# MCU.net
KiCad netlist of a schematic drawn in Altium Designer
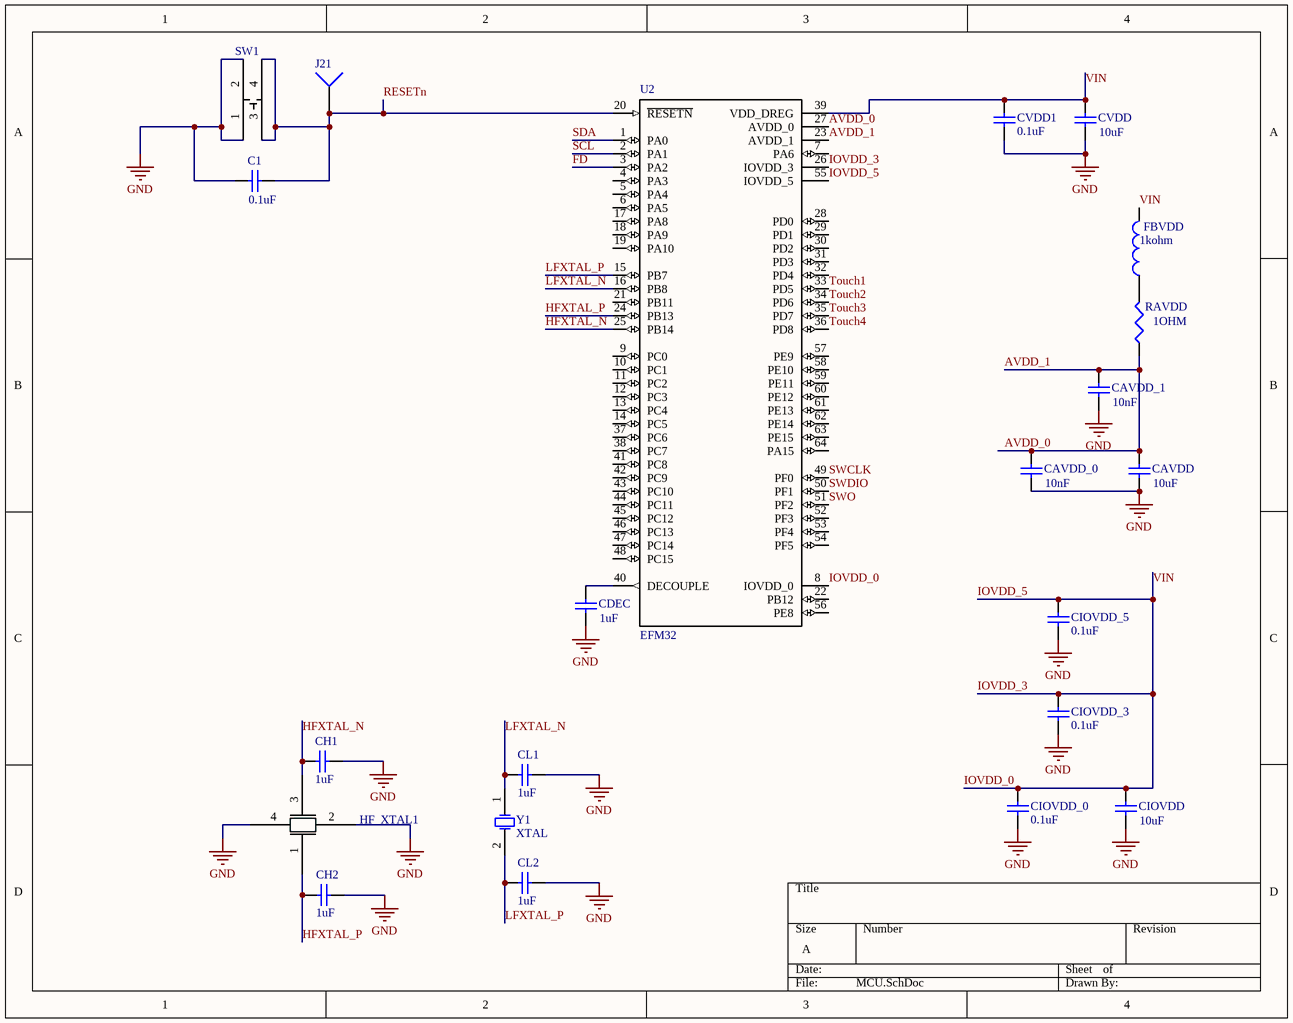
[diagram p0: MCU.SchDoc]

(export (version "E")
  (design (tool "Eeschema 10.0.6"))
  (components
    (comp (ref "C1")
      (value "0.1uF")
      (footprint "C1206")
      (description "CAP CER 0.1UF 16V Y5V 0603")
      (fields
        (field (name "DIGI-KEY PART NUMBER") "1276-1258-1-ND")
        (field (name "MANUFACTURER") "Samsung Electro-Mechanics")
      )
      (libsource (lib "Miscellaneous Devices") (part "Cap Semi"))
    )
    (comp (ref "CAVDD")
      (value "10uF")
      (footprint "C1206")
      (description "CL10A106MQ8NNNC")
      (fields
        (field (name "DIGI-KEY PART NUMBER") "1276-1119-1-ND")
        (field (name "MANUFACTURER") "Samsung Electro-Mechanics")
      )
      (libsource (lib "Miscellaneous Devices") (part "Cap Semi"))
    )
    (comp (ref "CAVDD_0")
      (value "10nF")
      (footprint "C1206")
      (description "CAP CER 10000PF 100V X7R 0603")
      (fields
        (field (name "DIGI-KEY PART NUMBER") "445-1305-1-ND")
        (field (name "MANUFACTURER") "TDK Corporation")
      )
      (libsource (lib "Miscellaneous Devices") (part "Cap Semi"))
    )
    (comp (ref "CAVDD_1")
      (value "10nF")
      (footprint "C1206")
      (description "CAP CER 10000PF 100V X7R 0603")
      (fields
        (field (name "DIGI-KEY PART NUMBER") "445-1305-1-ND")
        (field (name "MANUFACTURER") "TDK Corporation")
      )
      (libsource (lib "Miscellaneous Devices") (part "Cap Semi"))
    )
    (comp (ref "CDEC")
      (value "1uF")
      (footprint "C1206")
      (description "CAP CER 1UF 16V X7R 0603")
      (fields
        (field (name "DIGI-KEY PART NUMBER") "1276-6524-1-ND")
        (field (name "MANUFACTURER") "Samsung Electro-Mechanics")
      )
      (libsource (lib "Miscellaneous Devices") (part "Cap Semi"))
    )
    (comp (ref "CH1")
      (value "1uF")
      (footprint "C1206")
      (description "CAP CER 1UF 16V X7R 0603")
      (fields
        (field (name "DIGI-KEY PART NUMBER") "1276-6524-1-ND")
        (field (name "MANUFACTURER") "Samsung Electro-Mechanics")
      )
      (libsource (lib "Miscellaneous Devices") (part "Cap Semi"))
    )
    (comp (ref "CH2")
      (value "1uF")
      (footprint "C1206")
      (description "CAP CER 1UF 16V X7R 0603")
      (fields
        (field (name "DIGI-KEY PART NUMBER") "1276-6524-1-ND")
        (field (name "MANUFACTURER") "Samsung Electro-Mechanics")
      )
      (libsource (lib "Miscellaneous Devices") (part "Cap Semi"))
    )
    (comp (ref "CIOVDD")
      (value "10uF")
      (footprint "C1206")
      (description "CL10A106MQ8NNNC")
      (fields
        (field (name "DIGI-KEY PART NUMBER") "1276-1119-1-ND")
        (field (name "MANUFACTURER") "Samsung Electro-Mechanics")
      )
      (libsource (lib "Miscellaneous Devices") (part "Cap Semi"))
    )
    (comp (ref "CIOVDD_0")
      (value "0.1uF")
      (footprint "C1206")
      (description "CAP CER 0.1UF 16V Y5V 0603")
      (fields
        (field (name "DIGI-KEY PART NUMBER") "1276-1258-1-ND")
        (field (name "MANUFACTURER") "Samsung Electro-Mechanics")
      )
      (libsource (lib "Miscellaneous Devices") (part "Cap Semi"))
    )
    (comp (ref "CIOVDD_3")
      (value "0.1uF")
      (footprint "C1206")
      (description "CAP CER 0.1UF 16V Y5V 0603")
      (fields
        (field (name "DIGI-KEY PART NUMBER") "1276-1258-1-ND")
        (field (name "MANUFACTURER") "Samsung Electro-Mechanics")
      )
      (libsource (lib "Miscellaneous Devices") (part "Cap Semi"))
    )
    (comp (ref "CIOVDD_5")
      (value "0.1uF")
      (footprint "C1206")
      (description "CAP CER 0.1UF 16V Y5V 0603")
      (fields
        (field (name "DIGI-KEY PART NUMBER") "1276-1258-1-ND")
        (field (name "MANUFACTURER") "Samsung Electro-Mechanics")
      )
      (libsource (lib "Miscellaneous Devices") (part "Cap Semi"))
    )
    (comp (ref "CL1")
      (value "1uF")
      (footprint "C1206")
      (description "CAP CER 1UF 16V X7R 0603")
      (fields
        (field (name "DIGI-KEY PART NUMBER") "1276-6524-1-ND")
        (field (name "MANUFACTURER") "Samsung Electro-Mechanics")
      )
      (libsource (lib "Miscellaneous Devices") (part "Cap Semi"))
    )
    (comp (ref "CL2")
      (value "1uF")
      (footprint "C1206")
      (description "CAP CER 1UF 16V X7R 0603")
      (fields
        (field (name "DIGI-KEY PART NUMBER") "1276-6524-1-ND")
        (field (name "MANUFACTURER") "Samsung Electro-Mechanics")
      )
      (libsource (lib "Miscellaneous Devices") (part "Cap Semi"))
    )
    (comp (ref "CVDD")
      (value "10uF")
      (footprint "C1206")
      (description "CL10A106MQ8NNNC")
      (fields
        (field (name "DIGI-KEY PART NUMBER") "1276-1119-1-ND")
        (field (name "MANUFACTURER") "Samsung Electro-Mechanics")
      )
      (libsource (lib "Miscellaneous Devices") (part "Cap Semi"))
    )
    (comp (ref "CVDD1")
      (value "0.1uF")
      (footprint "C1206")
      (description "CAP CER 0.1UF 16V Y5V 0603")
      (fields
        (field (name "DIGI-KEY PART NUMBER") "1276-1258-1-ND")
        (field (name "MANUFACTURER") "Samsung Electro-Mechanics")
      )
      (libsource (lib "Miscellaneous Devices") (part "Cap Semi"))
    )
    (comp (ref "FBVDD")
      (value "1kohm")
      (footprint "0402-A")
      (description "FERRITE BEAD 1 KOHM 0603 1LN")
      (fields
        (field (name "DIGI-KEY PART NUMBER") "732-4484-1-ND")
        (field (name "MANUFACTURER") "Wurth Electronics Inc.")
      )
      (libsource (lib "Miscellaneous Devices") (part "Inductor"))
    )
    (comp (ref "HF_XTAL1")
      (value "Crystal_OSC")
      (footprint "HFXTAL")
      (fields
        (field (name "DIGI-KEY PART NUMBER") "1253-1120-1-ND")
        (field (name "MANUFACTURER") "Kyocera International Inc. Electronic Components")
        (field (name "MANUFACTURER PART NUMBER") "CX2016DB40000D0FLJCC")
      )
      (libsource (lib "EFM32PG12B500F1024GM48") (part "Crystal_OSC"))
    )
    (comp (ref "J21")
      (value "Socket")
      (footprint "PIN1")
      (fields (field (name "PUBLISHER") "Altium Limited"))
      (libsource (lib "Miscellaneous Connectors") (part "Socket"))
    )
    (comp (ref "RAVDD")
      (value "1OHM")
      (footprint "J1-0603")
      (description "RES SMD 1 OHM 1% 1/10W 0603")
      (fields (field (name "DIGI-KEY PART NUMBER") "311-1.00HRCT-ND") (field (name "MANUFACTURER") "Yageo"))
      (libsource (lib "Miscellaneous Devices") (part "Res3"))
    )
    (comp (ref "SW1")
      (value "Switch-PTS645")
      (footprint "Switch")
      (description "SWITCH TACTILE SPST-NO 0.05A 12V")
      (fields (field (name "DIGI-KEY PART NUMBER") "CKN9112CT-ND") (field (name "MANUFACTURER") "C&K"))
      (libsource (lib "EFM32PG12B500F1024GM48") (part "Switch-PTS645"))
    )
    (comp (ref "U2")
      (value "EFM32")
      (footprint "QFN-64")
      (description "IC MCU 32BIT 64KB FLASH 64QFN")
      (fields
        (field (name "DIGI-KEY PART NUMBER") "336-4841-1-ND")
        (field (name "MANUFACTURER") "Silicon Labs")
      )
      (libsource (lib "phone_cover_parts") (part "EFM32G232F128-QFP64"))
    )
    (comp (ref "Y1")
      (value "XTAL")
      (footprint "R38")
      (description "CRYSTAL 32.7680KHZ 7PF SMD")
      (fields
        (field (name "DIGI-KEY PART NUMBER") "535-9543-1-ND")
        (field (name "MANUFACTURER") "Abracon LLC")
      )
      (libsource (lib "Miscellaneous Devices") (part "XTAL"))
    )
  )
  (nets
    (net (code "1") (name "/AVDD_0") (class "Default")
      (node (ref "CAVDD") (pin "2") (pinfunction "2_2") (pintype "passive"))
      (node (ref "CAVDD_0") (pin "2") (pinfunction "2_2") (pintype "passive"))
      (node (ref "CAVDD_1") (pin "2") (pinfunction "2_2") (pintype "passive"))
      (node (ref "RAVDD") (pin "1") (pinfunction "1_1") (pintype "passive"))
      (node (ref "U2") (pin "23") (pinfunction "AVDD_1_23") (pintype "power_in"))
      (node (ref "U2") (pin "27") (pinfunction "AVDD_0_27") (pintype "power_in"))
    )
    (net (code "2") (name "/FD") (class "Default")
      (node (ref "U2") (pin "3") (pinfunction "PA2_3") (pintype "bidirectional"))
    )
    (net (code "3") (name "/HFXTAL_N") (class "Default")
      (node (ref "CH1") (pin "2") (pinfunction "2_2") (pintype "passive"))
      (node (ref "HF_XTAL1") (pin "3") (pinfunction "6_3") (pintype "passive"))
      (node (ref "U2") (pin "25") (pinfunction "PB14_25") (pintype "bidirectional"))
    )
    (net (code "4") (name "/HFXTAL_P") (class "Default")
      (node (ref "CH2") (pin "2") (pinfunction "2_2") (pintype "passive"))
      (node (ref "HF_XTAL1") (pin "1") (pinfunction "7_1") (pintype "passive"))
      (node (ref "U2") (pin "24") (pinfunction "PB13_24") (pintype "bidirectional"))
    )
    (net (code "5") (name "/IOVDD_0") (class "Default")
      (node (ref "CIOVDD") (pin "2") (pinfunction "2_2") (pintype "passive"))
      (node (ref "CIOVDD_0") (pin "2") (pinfunction "2_2") (pintype "passive"))
      (node (ref "CIOVDD_3") (pin "2") (pinfunction "2_2") (pintype "passive"))
      (node (ref "CIOVDD_5") (pin "2") (pinfunction "2_2") (pintype "passive"))
      (node (ref "CVDD") (pin "2") (pinfunction "2_2") (pintype "passive"))
      (node (ref "CVDD1") (pin "2") (pinfunction "2_2") (pintype "passive"))
      (node (ref "FBVDD") (pin "2") (pinfunction "2_2") (pintype "passive"))
      (node (ref "U2") (pin "26") (pinfunction "IOVDD_3_26") (pintype "power_in"))
      (node (ref "U2") (pin "39") (pinfunction "VDD_DREG_39") (pintype "power_in"))
      (node (ref "U2") (pin "55") (pinfunction "IOVDD_5_55") (pintype "power_in"))
      (node (ref "U2") (pin "8") (pinfunction "IOVDD_0_8") (pintype "power_in"))
    )
    (net (code "6") (name "/LFXTAL_N") (class "Default")
      (node (ref "CL1") (pin "2") (pinfunction "2_2") (pintype "passive"))
      (node (ref "U2") (pin "16") (pinfunction "PB8_16") (pintype "bidirectional"))
      (node (ref "Y1") (pin "1") (pinfunction "OSC1_1") (pintype "passive"))
    )
    (net (code "7") (name "/LFXTAL_P") (class "Default")
      (node (ref "CL2") (pin "1") (pinfunction "1_1") (pintype "passive"))
      (node (ref "U2") (pin "15") (pinfunction "PB7_15") (pintype "bidirectional"))
      (node (ref "Y1") (pin "2") (pinfunction "OSC2_2") (pintype "passive"))
    )
    (net (code "8") (name "/RESETn") (class "Default")
      (node (ref "C1") (pin "2") (pinfunction "2_2") (pintype "passive"))
      (node (ref "J21") (pin "1") (pinfunction "1_1") (pintype "passive"))
      (node (ref "SW1") (pin "3") (pinfunction "5_3") (pintype "passive"))
      (node (ref "SW1") (pin "4") (pinfunction "4_4") (pintype "passive"))
      (node (ref "U2") (pin "20") (pinfunction "~{RESETN}_20") (pintype "input"))
    )
    (net (code "9") (name "/SCL") (class "Default")
      (node (ref "U2") (pin "2") (pinfunction "PA1_2") (pintype "bidirectional"))
    )
    (net (code "10") (name "/SDA") (class "Default")
      (node (ref "U2") (pin "1") (pinfunction "PA0_1") (pintype "bidirectional"))
    )
    (net (code "11") (name "/SWCLK") (class "Default")
      (node (ref "U2") (pin "49") (pinfunction "PF0_49") (pintype "bidirectional"))
    )
    (net (code "12") (name "/SWDIO") (class "Default")
      (node (ref "U2") (pin "50") (pinfunction "PF1_50") (pintype "bidirectional"))
    )
    (net (code "13") (name "/SWO") (class "Default")
      (node (ref "U2") (pin "51") (pinfunction "PF2_51") (pintype "bidirectional"))
    )
    (net (code "14") (name "/Touch1") (class "Default")
      (node (ref "U2") (pin "33") (pinfunction "PD5_33") (pintype "bidirectional"))
    )
    (net (code "15") (name "/Touch2") (class "Default")
      (node (ref "U2") (pin "34") (pinfunction "PD6_34") (pintype "bidirectional"))
    )
    (net (code "16") (name "/Touch3") (class "Default")
      (node (ref "U2") (pin "35") (pinfunction "PD7_35") (pintype "bidirectional"))
    )
    (net (code "17") (name "/Touch4") (class "Default")
      (node (ref "U2") (pin "36") (pinfunction "PD8_36") (pintype "bidirectional"))
    )
    (net (code "18") (name "GND") (class "Default")
      (node (ref "C1") (pin "1") (pinfunction "1_1") (pintype "passive"))
      (node (ref "CAVDD") (pin "1") (pinfunction "1_1") (pintype "passive"))
      (node (ref "CAVDD_0") (pin "1") (pinfunction "1_1") (pintype "passive"))
      (node (ref "CAVDD_1") (pin "1") (pinfunction "1_1") (pintype "passive"))
      (node (ref "CDEC") (pin "1") (pinfunction "1_1") (pintype "passive"))
      (node (ref "CH1") (pin "1") (pinfunction "1_1") (pintype "passive"))
      (node (ref "CH2") (pin "1") (pinfunction "1_1") (pintype "passive"))
      (node (ref "CIOVDD") (pin "1") (pinfunction "1_1") (pintype "passive"))
      (node (ref "CIOVDD_0") (pin "1") (pinfunction "1_1") (pintype "passive"))
      (node (ref "CIOVDD_3") (pin "1") (pinfunction "1_1") (pintype "passive"))
      (node (ref "CIOVDD_5") (pin "1") (pinfunction "1_1") (pintype "passive"))
      (node (ref "CL1") (pin "1") (pinfunction "1_1") (pintype "passive"))
      (node (ref "CL2") (pin "2") (pinfunction "2_2") (pintype "passive"))
      (node (ref "CVDD") (pin "1") (pinfunction "1_1") (pintype "passive"))
      (node (ref "CVDD1") (pin "1") (pinfunction "1_1") (pintype "passive"))
      (node (ref "HF_XTAL1") (pin "2") (pinfunction "9_2") (pintype "passive"))
      (node (ref "HF_XTAL1") (pin "4") (pinfunction "8_4") (pintype "passive"))
      (node (ref "SW1") (pin "1") (pinfunction "5_1") (pintype "passive"))
      (node (ref "SW1") (pin "2") (pinfunction "6_2") (pintype "passive"))
    )
    (net (code "19") (name "Net-(FBVDD-Pad1)") (class "Default")
      (node (ref "FBVDD") (pin "1") (pinfunction "1_1") (pintype "passive"))
      (node (ref "RAVDD") (pin "2") (pinfunction "2_2") (pintype "passive"))
    )
    (net (code "20") (name "Net-(U2-DECOUPLE)") (class "Default")
      (node (ref "CDEC") (pin "2") (pinfunction "2_2") (pintype "passive"))
      (node (ref "U2") (pin "40") (pinfunction "DECOUPLE_40") (pintype "output"))
    )
    (net (code "21") (name "unconnected-(U2-PA3-Pad4)") (class "Default")
      (node (ref "U2") (pin "4") (pinfunction "PA3_4") (pintype "bidirectional"))
    )
    (net (code "22") (name "unconnected-(U2-PA4-Pad5)") (class "Default")
      (node (ref "U2") (pin "5") (pinfunction "PA4_5") (pintype "bidirectional"))
    )
    (net (code "23") (name "unconnected-(U2-PA5-Pad6)") (class "Default")
      (node (ref "U2") (pin "6") (pinfunction "PA5_6") (pintype "bidirectional"))
    )
    (net (code "24") (name "unconnected-(U2-PA6-Pad7)") (class "Default")
      (node (ref "U2") (pin "7") (pinfunction "PA6_7") (pintype "bidirectional"))
    )
    (net (code "25") (name "unconnected-(U2-PA8-Pad17)") (class "Default")
      (node (ref "U2") (pin "17") (pinfunction "PA8_17") (pintype "bidirectional"))
    )
    (net (code "26") (name "unconnected-(U2-PA9-Pad18)") (class "Default")
      (node (ref "U2") (pin "18") (pinfunction "PA9_18") (pintype "bidirectional"))
    )
    (net (code "27") (name "unconnected-(U2-PA10-Pad19)") (class "Default")
      (node (ref "U2") (pin "19") (pinfunction "PA10_19") (pintype "bidirectional"))
    )
    (net (code "28") (name "unconnected-(U2-PA15-Pad64)") (class "Default")
      (node (ref "U2") (pin "64") (pinfunction "PA15_64") (pintype "bidirectional"))
    )
    (net (code "29") (name "unconnected-(U2-PB11-Pad21)") (class "Default")
      (node (ref "U2") (pin "21") (pinfunction "PB11_21") (pintype "bidirectional"))
    )
    (net (code "30") (name "unconnected-(U2-PB12-Pad22)") (class "Default")
      (node (ref "U2") (pin "22") (pinfunction "PB12_22") (pintype "bidirectional"))
    )
    (net (code "31") (name "unconnected-(U2-PC0-Pad9)") (class "Default")
      (node (ref "U2") (pin "9") (pinfunction "PC0_9") (pintype "bidirectional"))
    )
    (net (code "32") (name "unconnected-(U2-PC1-Pad10)") (class "Default")
      (node (ref "U2") (pin "10") (pinfunction "PC1_10") (pintype "bidirectional"))
    )
    (net (code "33") (name "unconnected-(U2-PC2-Pad11)") (class "Default")
      (node (ref "U2") (pin "11") (pinfunction "PC2_11") (pintype "bidirectional"))
    )
    (net (code "34") (name "unconnected-(U2-PC3-Pad12)") (class "Default")
      (node (ref "U2") (pin "12") (pinfunction "PC3_12") (pintype "bidirectional"))
    )
    (net (code "35") (name "unconnected-(U2-PC4-Pad13)") (class "Default")
      (node (ref "U2") (pin "13") (pinfunction "PC4_13") (pintype "bidirectional"))
    )
    (net (code "36") (name "unconnected-(U2-PC5-Pad14)") (class "Default")
      (node (ref "U2") (pin "14") (pinfunction "PC5_14") (pintype "bidirectional"))
    )
    (net (code "37") (name "unconnected-(U2-PC6-Pad37)") (class "Default")
      (node (ref "U2") (pin "37") (pinfunction "PC6_37") (pintype "bidirectional"))
    )
    (net (code "38") (name "unconnected-(U2-PC7-Pad38)") (class "Default")
      (node (ref "U2") (pin "38") (pinfunction "PC7_38") (pintype "bidirectional"))
    )
    (net (code "39") (name "unconnected-(U2-PC8-Pad41)") (class "Default")
      (node (ref "U2") (pin "41") (pinfunction "PC8_41") (pintype "bidirectional"))
    )
    (net (code "40") (name "unconnected-(U2-PC9-Pad42)") (class "Default")
      (node (ref "U2") (pin "42") (pinfunction "PC9_42") (pintype "bidirectional"))
    )
    (net (code "41") (name "unconnected-(U2-PC10-Pad43)") (class "Default")
      (node (ref "U2") (pin "43") (pinfunction "PC10_43") (pintype "bidirectional"))
    )
    (net (code "42") (name "unconnected-(U2-PC11-Pad44)") (class "Default")
      (node (ref "U2") (pin "44") (pinfunction "PC11_44") (pintype "bidirectional"))
    )
    (net (code "43") (name "unconnected-(U2-PC12-Pad45)") (class "Default")
      (node (ref "U2") (pin "45") (pinfunction "PC12_45") (pintype "bidirectional"))
    )
    (net (code "44") (name "unconnected-(U2-PC13-Pad46)") (class "Default")
      (node (ref "U2") (pin "46") (pinfunction "PC13_46") (pintype "bidirectional"))
    )
    (net (code "45") (name "unconnected-(U2-PC14-Pad47)") (class "Default")
      (node (ref "U2") (pin "47") (pinfunction "PC14_47") (pintype "bidirectional"))
    )
    (net (code "46") (name "unconnected-(U2-PC15-Pad48)") (class "Default")
      (node (ref "U2") (pin "48") (pinfunction "PC15_48") (pintype "bidirectional"))
    )
    (net (code "47") (name "unconnected-(U2-PD0-Pad28)") (class "Default")
      (node (ref "U2") (pin "28") (pinfunction "PD0_28") (pintype "bidirectional"))
    )
    (net (code "48") (name "unconnected-(U2-PD1-Pad29)") (class "Default")
      (node (ref "U2") (pin "29") (pinfunction "PD1_29") (pintype "bidirectional"))
    )
    (net (code "49") (name "unconnected-(U2-PD2-Pad30)") (class "Default")
      (node (ref "U2") (pin "30") (pinfunction "PD2_30") (pintype "bidirectional"))
    )
    (net (code "50") (name "unconnected-(U2-PD3-Pad31)") (class "Default")
      (node (ref "U2") (pin "31") (pinfunction "PD3_31") (pintype "bidirectional"))
    )
    (net (code "51") (name "unconnected-(U2-PD4-Pad32)") (class "Default")
      (node (ref "U2") (pin "32") (pinfunction "PD4_32") (pintype "bidirectional"))
    )
    (net (code "52") (name "unconnected-(U2-PE8-Pad56)") (class "Default")
      (node (ref "U2") (pin "56") (pinfunction "PE8_56") (pintype "bidirectional"))
    )
    (net (code "53") (name "unconnected-(U2-PE9-Pad57)") (class "Default")
      (node (ref "U2") (pin "57") (pinfunction "PE9_57") (pintype "bidirectional"))
    )
    (net (code "54") (name "unconnected-(U2-PE10-Pad58)") (class "Default")
      (node (ref "U2") (pin "58") (pinfunction "PE10_58") (pintype "bidirectional"))
    )
    (net (code "55") (name "unconnected-(U2-PE11-Pad59)") (class "Default")
      (node (ref "U2") (pin "59") (pinfunction "PE11_59") (pintype "bidirectional"))
    )
    (net (code "56") (name "unconnected-(U2-PE12-Pad60)") (class "Default")
      (node (ref "U2") (pin "60") (pinfunction "PE12_60") (pintype "bidirectional"))
    )
    (net (code "57") (name "unconnected-(U2-PE13-Pad61)") (class "Default")
      (node (ref "U2") (pin "61") (pinfunction "PE13_61") (pintype "bidirectional"))
    )
    (net (code "58") (name "unconnected-(U2-PE14-Pad62)") (class "Default")
      (node (ref "U2") (pin "62") (pinfunction "PE14_62") (pintype "bidirectional"))
    )
    (net (code "59") (name "unconnected-(U2-PE15-Pad63)") (class "Default")
      (node (ref "U2") (pin "63") (pinfunction "PE15_63") (pintype "bidirectional"))
    )
    (net (code "60") (name "unconnected-(U2-PF3-Pad52)") (class "Default")
      (node (ref "U2") (pin "52") (pinfunction "PF3_52") (pintype "bidirectional"))
    )
    (net (code "61") (name "unconnected-(U2-PF4-Pad53)") (class "Default")
      (node (ref "U2") (pin "53") (pinfunction "PF4_53") (pintype "bidirectional"))
    )
    (net (code "62") (name "unconnected-(U2-PF5-Pad54)") (class "Default")
      (node (ref "U2") (pin "54") (pinfunction "PF5_54") (pintype "bidirectional"))
    )
  )
)
